# AD_Sensor_Module.net
KiCad netlist of a schematic drawn in Altium Designer
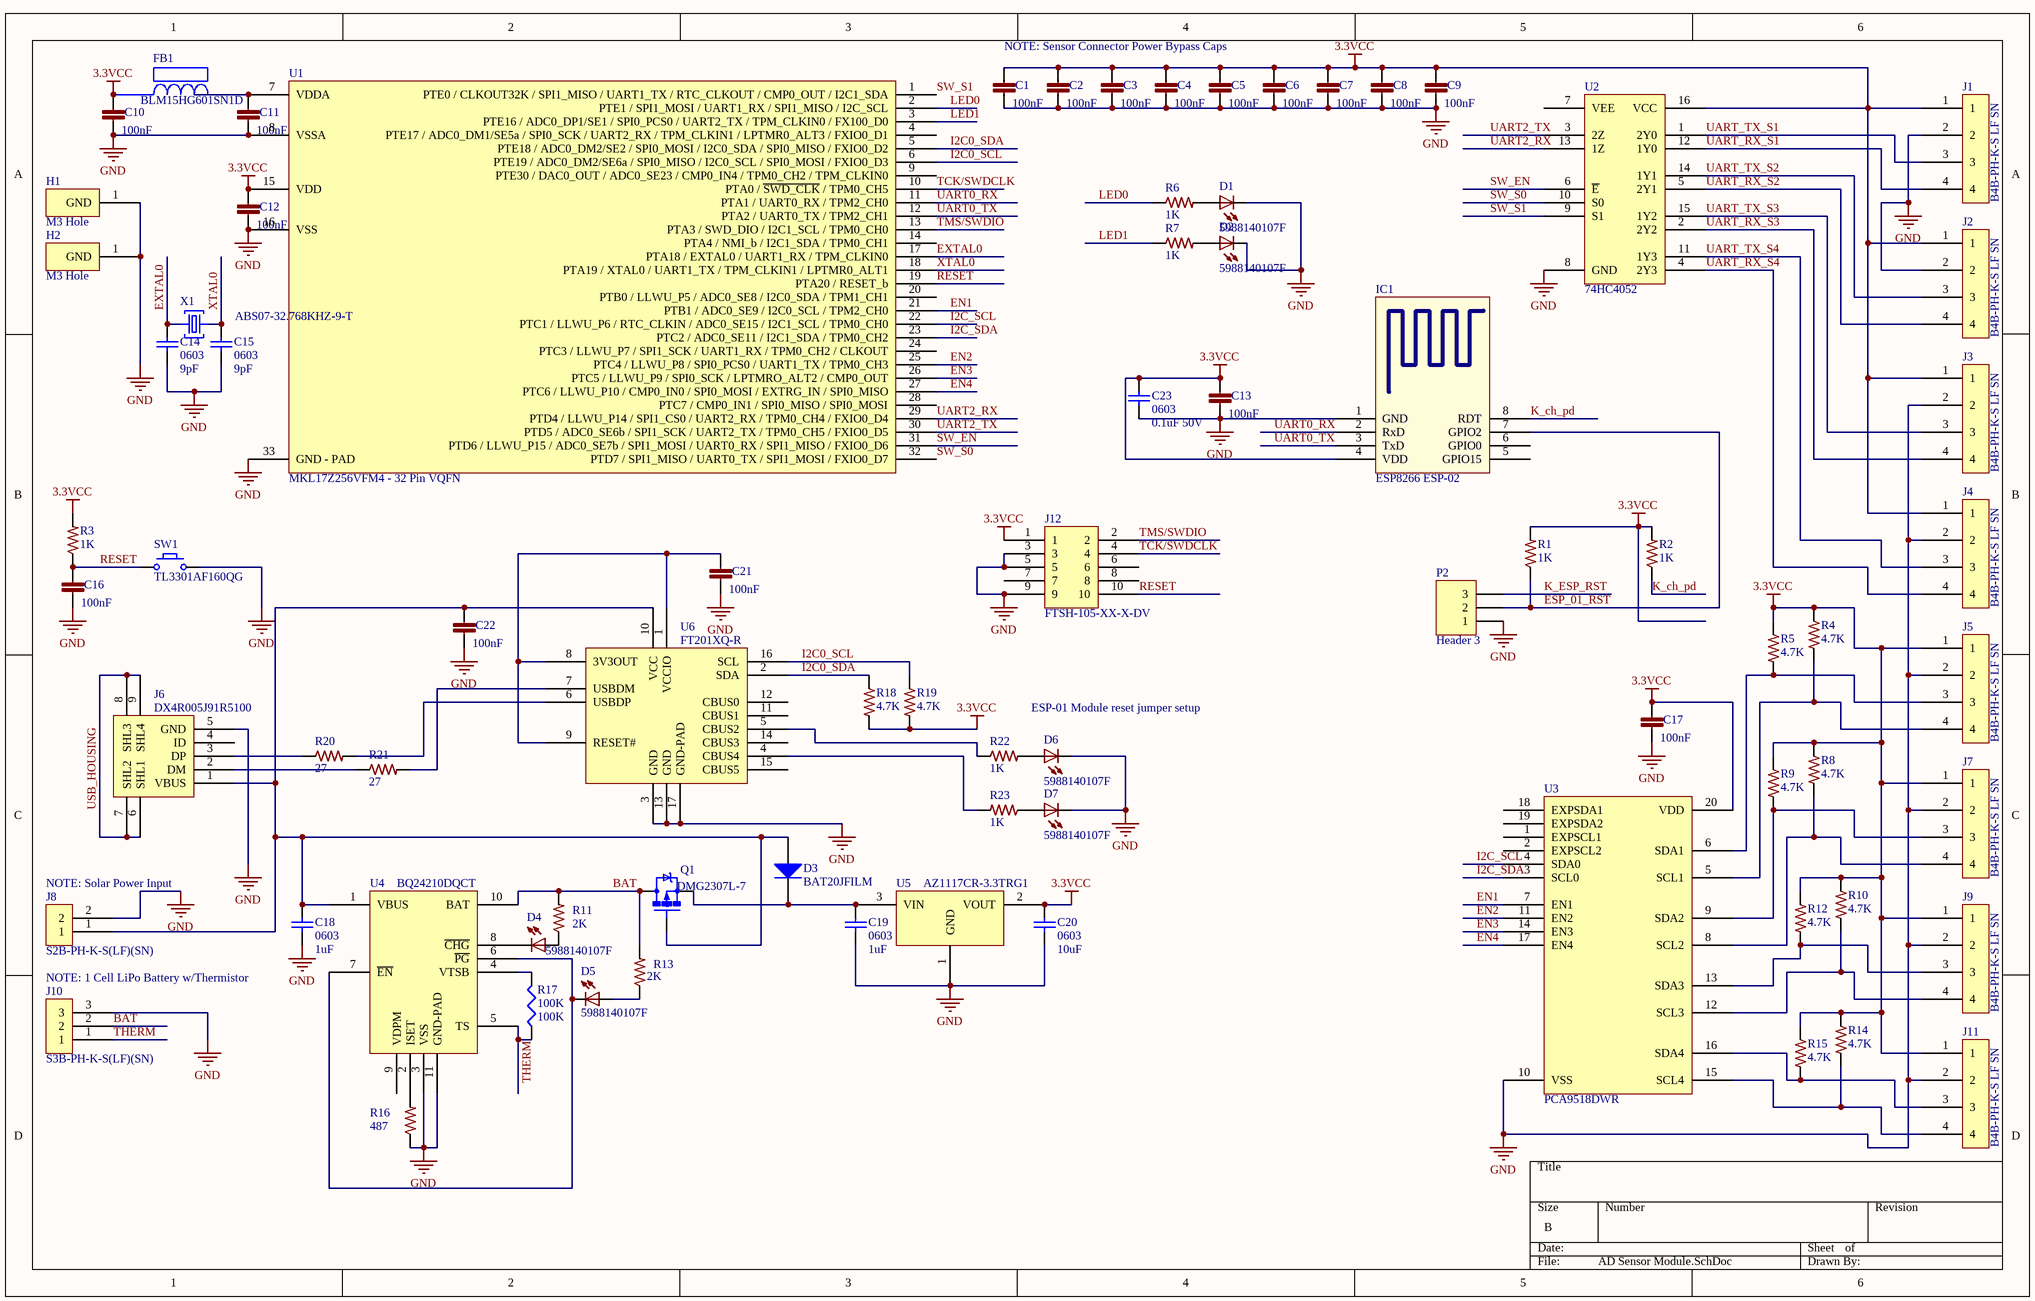
[diagram p0: AD Sensor Module.SchDoc]

(export (version "E")
  (design (tool "Eeschema 10.0.6"))
  (components
    (comp (ref "C1")
      (value "100nF")
      (footprint "C0402")
      (description "CAP CER 0402 100nF 16V 10% X7R")
      (fields
        (field (name "MANUFACTURERPARTNUMBER") "GRM155R71C104KA88D")
        (field (name "PUBLISHER") "UltiMachine")
      )
      (libsource (lib "3Delight") (part "GRM155R71C104KA88D"))
    )
    (comp (ref "C2")
      (value "100nF")
      (footprint "C0402")
      (description "CAP CER 0402 100nF 16V 10% X7R")
      (fields
        (field (name "MANUFACTURERPARTNUMBER") "GRM155R71C104KA88D")
        (field (name "PUBLISHER") "UltiMachine")
      )
      (libsource (lib "3Delight") (part "GRM155R71C104KA88D"))
    )
    (comp (ref "C3")
      (value "100nF")
      (footprint "C0402")
      (description "CAP CER 0402 100nF 16V 10% X7R")
      (fields
        (field (name "MANUFACTURERPARTNUMBER") "GRM155R71C104KA88D")
        (field (name "PUBLISHER") "UltiMachine")
      )
      (libsource (lib "3Delight") (part "GRM155R71C104KA88D"))
    )
    (comp (ref "C4")
      (value "100nF")
      (footprint "C0402")
      (description "CAP CER 0402 100nF 16V 10% X7R")
      (fields
        (field (name "MANUFACTURERPARTNUMBER") "GRM155R71C104KA88D")
        (field (name "PUBLISHER") "UltiMachine")
      )
      (libsource (lib "3Delight") (part "GRM155R71C104KA88D"))
    )
    (comp (ref "C5")
      (value "100nF")
      (footprint "C0402")
      (description "CAP CER 0402 100nF 16V 10% X7R")
      (fields
        (field (name "MANUFACTURERPARTNUMBER") "GRM155R71C104KA88D")
        (field (name "PUBLISHER") "UltiMachine")
      )
      (libsource (lib "3Delight") (part "GRM155R71C104KA88D"))
    )
    (comp (ref "C6")
      (value "100nF")
      (footprint "C0402")
      (description "CAP CER 0402 100nF 16V 10% X7R")
      (fields
        (field (name "MANUFACTURERPARTNUMBER") "GRM155R71C104KA88D")
        (field (name "PUBLISHER") "UltiMachine")
      )
      (libsource (lib "3Delight") (part "GRM155R71C104KA88D"))
    )
    (comp (ref "C7")
      (value "100nF")
      (footprint "C0402")
      (description "CAP CER 0402 100nF 16V 10% X7R")
      (fields
        (field (name "MANUFACTURERPARTNUMBER") "GRM155R71C104KA88D")
        (field (name "PUBLISHER") "UltiMachine")
      )
      (libsource (lib "3Delight") (part "GRM155R71C104KA88D"))
    )
    (comp (ref "C8")
      (value "100nF")
      (footprint "C0402")
      (description "CAP CER 0402 100nF 16V 10% X7R")
      (fields
        (field (name "MANUFACTURERPARTNUMBER") "GRM155R71C104KA88D")
        (field (name "PUBLISHER") "UltiMachine")
      )
      (libsource (lib "3Delight") (part "GRM155R71C104KA88D"))
    )
    (comp (ref "C9")
      (value "100nF")
      (footprint "C0402")
      (description "CAP CER 0402 100nF 16V 10% X7R")
      (fields
        (field (name "MANUFACTURERPARTNUMBER") "GRM155R71C104KA88D")
        (field (name "PUBLISHER") "UltiMachine")
      )
      (libsource (lib "3Delight") (part "GRM155R71C104KA88D"))
    )
    (comp (ref "C10")
      (value "100nF")
      (footprint "C0402")
      (description "CAP CER 0402 100nF 16V 10% X7R")
      (fields
        (field (name "MANUFACTURERPARTNUMBER") "GRM155R71C104KA88D")
        (field (name "PUBLISHER") "UltiMachine")
      )
      (libsource (lib "3Delight") (part "GRM155R71C104KA88D"))
    )
    (comp (ref "C11")
      (value "100nF")
      (footprint "C0402")
      (description "CAP CER 0402 100nF 16V 10% X7R")
      (fields
        (field (name "MANUFACTURERPARTNUMBER") "GRM155R71C104KA88D")
        (field (name "PUBLISHER") "UltiMachine")
      )
      (libsource (lib "3Delight") (part "GRM155R71C104KA88D"))
    )
    (comp (ref "C12")
      (value "100nF")
      (footprint "C0402")
      (description "CAP CER 0402 100nF 16V 10% X7R")
      (fields
        (field (name "MANUFACTURERPARTNUMBER") "GRM155R71C104KA88D")
        (field (name "PUBLISHER") "UltiMachine")
      )
      (libsource (lib "3Delight") (part "GRM155R71C104KA88D"))
    )
    (comp (ref "C13")
      (value "100nF")
      (footprint "C0402")
      (description "CAP CER 0402 100nF 16V 10% X7R")
      (fields
        (field (name "MANUFACTURERPARTNUMBER") "GRM155R71C104KA88D")
        (field (name "PUBLISHER") "UltiMachine")
      )
      (libsource (lib "3Delight") (part "GRM155R71C104KA88D"))
    )
    (comp (ref "C14")
      (value "0603")
      (footprint "C0603")
      (description "CAP CER 9PF 50V NP0 0603")
      (fields
        (field (name "MFR") "Samsung Electro-Mechanics America, Inc.")
        (field (name "TOLERANCE") "10%")
        (field (name "ALTIUM_VALUE") "9pF")
        (field (name "DESIGNER") "Adam Vadala-Roth")
      )
      (libsource (lib "Sensor Package") (part "CL10C090CB8NNNC"))
    )
    (comp (ref "C15")
      (value "0603")
      (footprint "C0603")
      (description "CAP CER 9PF 50V NP0 0603")
      (fields
        (field (name "MFR") "Samsung Electro-Mechanics America, Inc.")
        (field (name "TOLERANCE") "10%")
        (field (name "ALTIUM_VALUE") "9pF")
        (field (name "DESIGNER") "Adam Vadala-Roth")
      )
      (libsource (lib "Sensor Package") (part "CL10C090CB8NNNC"))
    )
    (comp (ref "C16")
      (value "100nF")
      (footprint "C0402")
      (description "CAP CER 0402 100nF 16V 10% X7R")
      (fields
        (field (name "MANUFACTURERPARTNUMBER") "GRM155R71C104KA88D")
        (field (name "PUBLISHER") "UltiMachine")
      )
      (libsource (lib "3Delight") (part "GRM155R71C104KA88D"))
    )
    (comp (ref "C17")
      (value "100nF")
      (footprint "C0402")
      (description "CAP CER 0402 100nF 16V 10% X7R")
      (fields
        (field (name "MANUFACTURERPARTNUMBER") "GRM155R71C104KA88D")
        (field (name "PUBLISHER") "UltiMachine")
      )
      (libsource (lib "3Delight") (part "GRM155R71C104KA88D"))
    )
    (comp (ref "C18")
      (value "0603")
      (footprint "C0603")
      (description "CAP CER 1UF 25V X5R 0402")
      (fields
        (field (name "MFR PART #") "CL05A105KA5NQNC")
        (field (name "MFR") "Samsung")
        (field (name "ALTIUM_VALUE") "1uF")
      )
      (libsource (lib "Sensor Package") (part "CL05A105KA5NQNC"))
    )
    (comp (ref "C19")
      (value "0603")
      (footprint "C0603")
      (description "CAP CER 1UF 25V X5R 0402")
      (fields
        (field (name "MFR PART #") "CL05A105KA5NQNC")
        (field (name "MFR") "Samsung")
        (field (name "ALTIUM_VALUE") "1uF")
      )
      (libsource (lib "Sensor Package") (part "CL05A105KA5NQNC"))
    )
    (comp (ref "C20")
      (value "0603")
      (footprint "C0603")
      (description "CAP CER 10UF 6.3V X5R 0603")
      (fields
        (field (name "MFR") "Samsung Electro-Mechanics America, Inc.")
        (field (name "TOLERANCE") "10%")
        (field (name "ALTIUM_VALUE") "10uF")
        (field (name "DESIGNER") "Adam Vadala-Roth")
      )
      (libsource (lib "Sensor Package") (part "CL10A106KQ8NNNC"))
    )
    (comp (ref "C21")
      (value "100nF")
      (footprint "C0402")
      (description "CAP CER 0402 100nF 16V 10% X7R")
      (fields
        (field (name "MANUFACTURERPARTNUMBER") "GRM155R71C104KA88D")
        (field (name "PUBLISHER") "UltiMachine")
      )
      (libsource (lib "3Delight") (part "GRM155R71C104KA88D"))
    )
    (comp (ref "C22")
      (value "100nF")
      (footprint "C0402")
      (description "CAP CER 0402 100nF 16V 10% X7R")
      (fields
        (field (name "MANUFACTURERPARTNUMBER") "GRM155R71C104KA88D")
        (field (name "PUBLISHER") "UltiMachine")
      )
      (libsource (lib "3Delight") (part "GRM155R71C104KA88D"))
    )
    (comp (ref "C23")
      (value "0603")
      (footprint "C0603")
      (description "CAP CER 0.1UF 50V 10% X7R 0603")
      (fields
        (field (name "MFR PART #") "CL10B104KB8SFNC")
        (field (name "MFR") "Samsung")
        (field (name "ALTIUM_VALUE") "0.1uF 50V")
      )
      (libsource (lib "Sensor Package") (part "CL10B104KB8SFNC"))
    )
    (comp (ref "D1")
      (value "5988140107F")
      (footprint "LED2012120")
      (description "LED 0805 Yellow")
      (fields (field (name "PUBLISHER") "UltiMachine"))
      (libsource (lib "Tigershark3D") (part "5988140107F"))
    )
    (comp (ref "D2")
      (value "5988140107F")
      (footprint "LED2012120")
      (description "LED 0805 Yellow")
      (fields (field (name "PUBLISHER") "UltiMachine"))
      (libsource (lib "Tigershark3D") (part "5988140107F"))
    )
    (comp (ref "D3")
      (value "BAT20JFILM")
      (footprint "BAT20JFILM - DIOM1712X11N")
      (description "DIODE SCHOTTKY 23V 1A SOD323")
      (fields
        (field (name "MFR") "ST Microelectronics")
        (field (name "PUBLISHER") "Altium Limited")
        (field (name "DESIGNER") "Adam J Valala-Roth")
      )
      (libsource (lib "Sensor Package") (part "BAT20JFILM"))
    )
    (comp (ref "D4")
      (value "5988140107F")
      (footprint "LED2012120")
      (description "LED 0805 Yellow")
      (fields (field (name "PUBLISHER") "UltiMachine"))
      (libsource (lib "Tigershark3D") (part "5988140107F"))
    )
    (comp (ref "D5")
      (value "5988140107F")
      (footprint "LED2012120")
      (description "LED 0805 Yellow")
      (fields (field (name "PUBLISHER") "UltiMachine"))
      (libsource (lib "Tigershark3D") (part "5988140107F"))
    )
    (comp (ref "D6")
      (value "5988140107F")
      (footprint "LED2012120")
      (description "LED 0805 Yellow")
      (fields (field (name "PUBLISHER") "UltiMachine"))
      (libsource (lib "Tigershark3D") (part "5988140107F"))
    )
    (comp (ref "D7")
      (value "5988140107F")
      (footprint "LED2012120")
      (description "LED 0805 Yellow")
      (fields (field (name "PUBLISHER") "UltiMachine"))
      (libsource (lib "Tigershark3D") (part "5988140107F"))
    )
    (comp (ref "FB1")
      (value "BLM15HG601SN1D")
      (footprint "BLM18PG121SN1D")
      (libsource (lib "Sensor Package") (part "BLM15HG601SN1D"))
    )
    (comp (ref "H1")
      (value "M3 Hole")
      (footprint "Hole-3mm")
      (description "3mm Hole")
      (libsource (lib "Sensor Package") (part "Hole"))
    )
    (comp (ref "H2")
      (value "M3 Hole")
      (footprint "Hole-3mm")
      (description "3mm Hole")
      (libsource (lib "Sensor Package") (part "Hole"))
    )
    (comp (ref "IC1")
      (value "ESP8266 ESP-02")
      (footprint "ESP8266 ESP-02")
      (libsource (lib "ESP8266") (part "ESP8266 ESP-02"))
    )
    (comp (ref "J1")
      (value "B4B-PH-K-S LF SN")
      (footprint "B4B-PH-K-S(LF)(SN)")
      (description "CONN HEADER PH TOP 4POS 2MM")
      (fields (field (name "MFR") "JST") (field (name "DESIGNER") "Adam Vadala-Roth"))
      (libsource (lib "Sensor Package") (part "B4B-PH-K-S LF SN"))
    )
    (comp (ref "J2")
      (value "B4B-PH-K-S LF SN")
      (footprint "B4B-PH-K-S(LF)(SN)")
      (description "CONN HEADER PH TOP 4POS 2MM")
      (fields (field (name "MFR") "JST") (field (name "DESIGNER") "Adam Vadala-Roth"))
      (libsource (lib "Sensor Package") (part "B4B-PH-K-S LF SN"))
    )
    (comp (ref "J3")
      (value "B4B-PH-K-S LF SN")
      (footprint "B4B-PH-K-S(LF)(SN)")
      (description "CONN HEADER PH TOP 4POS 2MM")
      (fields (field (name "MFR") "JST") (field (name "DESIGNER") "Adam Vadala-Roth"))
      (libsource (lib "Sensor Package") (part "B4B-PH-K-S LF SN"))
    )
    (comp (ref "J4")
      (value "B4B-PH-K-S LF SN")
      (footprint "B4B-PH-K-S(LF)(SN)")
      (description "CONN HEADER PH TOP 4POS 2MM")
      (fields (field (name "MFR") "JST") (field (name "DESIGNER") "Adam Vadala-Roth"))
      (libsource (lib "Sensor Package") (part "B4B-PH-K-S LF SN"))
    )
    (comp (ref "J5")
      (value "B4B-PH-K-S LF SN")
      (footprint "B4B-PH-K-S(LF)(SN)")
      (description "CONN HEADER PH TOP 4POS 2MM")
      (fields (field (name "MFR") "JST") (field (name "DESIGNER") "Adam Vadala-Roth"))
      (libsource (lib "Sensor Package") (part "B4B-PH-K-S LF SN"))
    )
    (comp (ref "J6")
      (value "DX4R005J91R5100")
      (footprint "Micro USB Circular Holes Only")
      (description "Micro USB Jack B")
      (libsource (lib "Sensor Package") (part "Micro USB"))
    )
    (comp (ref "J7")
      (value "B4B-PH-K-S LF SN")
      (footprint "B4B-PH-K-S(LF)(SN)")
      (description "CONN HEADER PH TOP 4POS 2MM")
      (fields (field (name "MFR") "JST") (field (name "DESIGNER") "Adam Vadala-Roth"))
      (libsource (lib "Sensor Package") (part "B4B-PH-K-S LF SN"))
    )
    (comp (ref "J8")
      (value "S2B-PH-K-S(LF)(SN)")
      (footprint "S2B-PH-K-S(LF)(SN)")
      (description "CONN HEADER PH SIDE 2POS 2MM")
      (fields (field (name "MFR") "JST") (field (name "DESIGNER") "Adam Vadala-Roth"))
      (libsource (lib "Sensor Package") (part "S2B-PH-K-S(LF)(SN)"))
    )
    (comp (ref "J9")
      (value "B4B-PH-K-S LF SN")
      (footprint "B4B-PH-K-S(LF)(SN)")
      (description "CONN HEADER PH TOP 4POS 2MM")
      (fields (field (name "MFR") "JST") (field (name "DESIGNER") "Adam Vadala-Roth"))
      (libsource (lib "Sensor Package") (part "B4B-PH-K-S LF SN"))
    )
    (comp (ref "J10")
      (value "S3B-PH-K-S(LF)(SN)")
      (footprint "S3B-PH-K-S(LF)(SN)")
      (description "CONN HEADER PH SIDE 2POS 2MM")
      (fields (field (name "MFR") "JST") (field (name "DESIGNER") "Adam Vadala-Roth"))
      (libsource (lib "Sensor Package") (part "S3B-PH-K-S(LF)(SN)"))
    )
    (comp (ref "J11")
      (value "B4B-PH-K-S LF SN")
      (footprint "B4B-PH-K-S(LF)(SN)")
      (description "CONN HEADER PH TOP 4POS 2MM")
      (fields (field (name "MFR") "JST") (field (name "DESIGNER") "Adam Vadala-Roth"))
      (libsource (lib "Sensor Package") (part "B4B-PH-K-S LF SN"))
    )
    (comp (ref "J12")
      (value "FTSH-105-XX-X-DV")
      (footprint "FTSH-105-XX-X-DV")
      (description "FTSH-105-XX-X-DV ARM COrtex JTAG")
      (fields (field (name "DESIGNER") "*"))
      (libsource (lib "Sensor Package") (part "FTSH-105-XX-X-DV"))
    )
    (comp (ref "P2")
      (value "Header 3")
      (footprint "HDR1X3")
      (description "Header, 3-Pin")
      (fields (field (name "PUBLISHER") "Altium Limited"))
      (libsource (lib "Miscellaneous Connectors") (part "Header 3"))
    )
    (comp (ref "Q1")
      (value "DMG2307L-7")
      (footprint "DMG2307L-7 - SOT92P240X102-3N")
      (description "MOSFET P-CH 30V 2.5A SOT-23")
      (fields (field (name "MFR") "Diodes Incorporated") (field (name "PUBLISHER") "Adam Vadala-Roth"))
      (libsource (lib "Sensor Package") (part "DMG2307L-7"))
    )
    (comp (ref "R1")
      (value "1K")
      (footprint "R0603")
      (description "RES 0603 1K 100mW 1%")
      (fields
        (field (name "MANUFACTURERPARTNUMBER") "ERJ-3EKF1001V")
        (field (name "PUBLISHER") "UltiMachine")
      )
      (libsource (lib "3Delight") (part "ERJ-3EKF1001V"))
    )
    (comp (ref "R2")
      (value "1K")
      (footprint "R0603")
      (description "RES 0603 1K 100mW 1%")
      (fields
        (field (name "MANUFACTURERPARTNUMBER") "ERJ-3EKF1001V")
        (field (name "PUBLISHER") "UltiMachine")
      )
      (libsource (lib "3Delight") (part "ERJ-3EKF1001V"))
    )
    (comp (ref "R3")
      (value "1K")
      (footprint "R0603")
      (description "RES 0603 1K 100mW 1%")
      (fields
        (field (name "MANUFACTURERPARTNUMBER") "ERJ-3EKF1001V")
        (field (name "PUBLISHER") "UltiMachine")
      )
      (libsource (lib "3Delight") (part "ERJ-3EKF1001V"))
    )
    (comp (ref "R4")
      (value "4.7K")
      (footprint "R0603")
      (description "RES 0603 4.7K 100mW 1%")
      (fields (field (name "MANUFACTURERPARTNUMBER") "ERJ3EKF4701V") (field (name "PUBLISHER") "UltiMachine"))
      (libsource (lib "Tigershark3D") (part "ERJ3EKF4701V"))
    )
    (comp (ref "R5")
      (value "4.7K")
      (footprint "R0603")
      (description "RES 0603 4.7K 100mW 1%")
      (fields (field (name "MANUFACTURERPARTNUMBER") "ERJ3EKF4701V") (field (name "PUBLISHER") "UltiMachine"))
      (libsource (lib "Tigershark3D") (part "ERJ3EKF4701V"))
    )
    (comp (ref "R6")
      (value "1K")
      (footprint "R0603")
      (description "RES 0603 1K 100mW 1%")
      (fields
        (field (name "MANUFACTURERPARTNUMBER") "ERJ-3EKF1001V")
        (field (name "PUBLISHER") "UltiMachine")
      )
      (libsource (lib "Tigershark3D") (part "ERJ-3EKF1001V"))
    )
    (comp (ref "R7")
      (value "1K")
      (footprint "R0603")
      (description "RES 0603 1K 100mW 1%")
      (fields
        (field (name "MANUFACTURERPARTNUMBER") "ERJ-3EKF1001V")
        (field (name "PUBLISHER") "UltiMachine")
      )
      (libsource (lib "Tigershark3D") (part "ERJ-3EKF1001V"))
    )
    (comp (ref "R8")
      (value "4.7K")
      (footprint "R0603")
      (description "RES 0603 4.7K 100mW 1%")
      (fields (field (name "MANUFACTURERPARTNUMBER") "ERJ3EKF4701V") (field (name "PUBLISHER") "UltiMachine"))
      (libsource (lib "Tigershark3D") (part "ERJ3EKF4701V"))
    )
    (comp (ref "R9")
      (value "4.7K")
      (footprint "R0603")
      (description "RES 0603 4.7K 100mW 1%")
      (fields (field (name "MANUFACTURERPARTNUMBER") "ERJ3EKF4701V") (field (name "PUBLISHER") "UltiMachine"))
      (libsource (lib "Tigershark3D") (part "ERJ3EKF4701V"))
    )
    (comp (ref "R10")
      (value "4.7K")
      (footprint "R0603")
      (description "RES 0603 4.7K 100mW 1%")
      (fields (field (name "MANUFACTURERPARTNUMBER") "ERJ3EKF4701V") (field (name "PUBLISHER") "UltiMachine"))
      (libsource (lib "Tigershark3D") (part "ERJ3EKF4701V"))
    )
    (comp (ref "R11")
      (value "2K")
      (footprint "R0805")
      (description "RES SMD 2K OHM 1% 1/8W 0805")
      (fields
        (field (name "MFR") "Panasonic Electronic Components")
        (field (name "TOLERANCE") "1%")
        (field (name "DESIGNER") "Adam Vadala-Roth")
      )
      (libsource (lib "Sensor Package") (part "ERJ-6ENF2001V"))
    )
    (comp (ref "R12")
      (value "4.7K")
      (footprint "R0603")
      (description "RES 0603 4.7K 100mW 1%")
      (fields (field (name "MANUFACTURERPARTNUMBER") "ERJ3EKF4701V") (field (name "PUBLISHER") "UltiMachine"))
      (libsource (lib "Tigershark3D") (part "ERJ3EKF4701V"))
    )
    (comp (ref "R13")
      (value "2K")
      (footprint "R0805")
      (description "RES SMD 2K OHM 1% 1/8W 0805")
      (fields
        (field (name "MFR") "Panasonic Electronic Components")
        (field (name "TOLERANCE") "1%")
        (field (name "DESIGNER") "Adam Vadala-Roth")
      )
      (libsource (lib "Sensor Package") (part "ERJ-6ENF2001V"))
    )
    (comp (ref "R14")
      (value "4.7K")
      (footprint "R0603")
      (description "RES 0603 4.7K 100mW 1%")
      (fields (field (name "MANUFACTURERPARTNUMBER") "ERJ3EKF4701V") (field (name "PUBLISHER") "UltiMachine"))
      (libsource (lib "Tigershark3D") (part "ERJ3EKF4701V"))
    )
    (comp (ref "R15")
      (value "4.7K")
      (footprint "R0603")
      (description "RES 0603 4.7K 100mW 1%")
      (fields (field (name "MANUFACTURERPARTNUMBER") "ERJ3EKF4701V") (field (name "PUBLISHER") "UltiMachine"))
      (libsource (lib "Tigershark3D") (part "ERJ3EKF4701V"))
    )
    (comp (ref "R16")
      (value "487")
      (footprint "R0402")
      (description "RES SMD 487 OHM 1% 1/16W 0402")
      (fields
        (field (name "MFR") "Samsung Electro-Mechanics America, Inc.")
        (field (name "TOLERANCE") "1%")
        (field (name "DESIGNER") "Adam Vadala-Roth")
      )
      (libsource (lib "Sensor Package") (part "RC1005F4870CS"))
    )
    (comp (ref "R17")
      (value "100K")
      (footprint "R0402")
      (description "Standin 0402")
      (fields (field (name "ALTIUM_VALUE") "100K"))
      (libsource (lib "Sensor Package") (part "Standin 0402"))
    )
    (comp (ref "R18")
      (value "4.7K")
      (footprint "R0603")
      (description "RES 0603 4.7K 100mW 1%")
      (fields (field (name "MANUFACTURERPARTNUMBER") "ERJ3EKF4701V") (field (name "PUBLISHER") "UltiMachine"))
      (libsource (lib "Tigershark3D") (part "ERJ3EKF4701V"))
    )
    (comp (ref "R19")
      (value "4.7K")
      (footprint "R0603")
      (description "RES 0603 4.7K 100mW 1%")
      (fields (field (name "MANUFACTURERPARTNUMBER") "ERJ3EKF4701V") (field (name "PUBLISHER") "UltiMachine"))
      (libsource (lib "Tigershark3D") (part "ERJ3EKF4701V"))
    )
    (comp (ref "R20")
      (value "27")
      (footprint "R0402")
      (description "RES SMD 27 OHM 0.5% 1/16W 0402")
      (fields
        (field (name "MFR") "Susumu")
        (field (name "TOLERANCE") "0.5%")
        (field (name "DESIGNER") "Adam Vadala-Roth")
      )
      (libsource (lib "Sensor Package") (part "RR0510R-270-D"))
    )
    (comp (ref "R21")
      (value "27")
      (footprint "R0402")
      (description "RES SMD 27 OHM 0.5% 1/16W 0402")
      (fields
        (field (name "MFR") "Susumu")
        (field (name "TOLERANCE") "0.5%")
        (field (name "DESIGNER") "Adam Vadala-Roth")
      )
      (libsource (lib "Sensor Package") (part "RR0510R-270-D"))
    )
    (comp (ref "R22")
      (value "1K")
      (footprint "R0603")
      (description "RES 0603 1K 100mW 1%")
      (fields
        (field (name "MANUFACTURERPARTNUMBER") "ERJ-3EKF1001V")
        (field (name "PUBLISHER") "UltiMachine")
      )
      (libsource (lib "Tigershark3D") (part "ERJ-3EKF1001V"))
    )
    (comp (ref "R23")
      (value "1K")
      (footprint "R0603")
      (description "RES 0603 1K 100mW 1%")
      (fields
        (field (name "MANUFACTURERPARTNUMBER") "ERJ-3EKF1001V")
        (field (name "PUBLISHER") "UltiMachine")
      )
      (libsource (lib "Tigershark3D") (part "ERJ-3EKF1001V"))
    )
    (comp (ref "SW1")
      (value "TL3301AF160QG")
      (footprint "TL3301AF160QG")
      (libsource (lib "MongoosMini") (part "TL3301AF160QG"))
    )
    (comp (ref "U1")
      (value "MKL17Z256VFM4 - 32 Pin VQFN")
      (footprint "MKL17Z256VFM4 - QFN50P500X500X65_HS-33N")
      (description "ARM Cortex M0+ Microcontroller for Low Power Applications, MKL1x Series")
      (fields
        (field (name "MFR") "NXP - FreeScale")
        (field (name "VOLTAGE") "1.7-3.3VDC")
        (field (name "DESIGNER") "Adam Vadala-Roth")
      )
      (libsource (lib "Sensor Package") (part "MKL17Z256VFM4 - 32 Pin VQFN"))
    )
    (comp (ref "U2")
      (value "74HC4052")
      (footprint "74HC4052")
      (description "Dual 4-channel analog multiplexer/demultiplexer")
      (fields (field (name "MFR") "NXP"))
      (libsource (lib "Sensor Package") (part "74HC4052"))
    )
    (comp (ref "U3")
      (value "PCA9518DWR")
      (footprint "PCA9518DWR")
      (description "IC EXPANDABLE 5CH I2C HUB 20SOIC")
      (fields (field (name "MFR") "Ti"))
      (libsource (lib "Sensor Package") (part "PCA9518DWR"))
    )
    (comp (ref "U4")
      (value "BQ24210DQCT")
      (footprint "bq24210 - QFN50P300X200X80-10N")
      (description "IC BATT CHARGER LI-ION 10WSON (VBUS and Solar Voltaic Cell)")
      (fields (field (name "MFR") "Texas Instruments") (field (name "DESIGNER") "Adam J Vadala-Roth"))
      (libsource (lib "Sensor Package") (part "BQ24210DQCT"))
    )
    (comp (ref "U5")
      (value "AZ1117CR-3.3TRG1")
      (footprint "AZ1117CR-3.3TRG1 - SOT89-150P410X160-3N")
      (description "IC REG LDO 3.3V 0.8A SOT89")
      (fields
        (field (name "MFR") "Diodes Inc")
        (field (name "VOLTAGE") "3V3")
        (field (name "DESIGNER") "Adam Vadala-Roth")
      )
      (libsource (lib "Sensor Package") (part "AZ1117CR-3.3TRG1"))
    )
    (comp (ref "U6")
      (value "FT201XQ-R")
      (footprint "FT201XQ-R - QFN65P400X400X80_HS-17N")
      (description "IC USB FS I2C 16QFN")
      (fields
        (field (name "MFR") "FTDI")
        (field (name "VOLTAGE") "3V3/5V")
        (field (name "DESIGNER") "Adam Vadala-Roth")
      )
      (libsource (lib "Sensor Package") (part "FT201XQ-R"))
    )
    (comp (ref "X1")
      (value "ABS07-32.768KHZ-9-T")
      (footprint "ABS07-32.768KHZ-9-T")
      (description "32.768kHz ±20ppm Crystal 9pF 70 kOhm -40°C ~ 85°C Surface Mount 2-SMD")
      (fields
        (field (name "MFR") "Abracon LLC")
        (field (name "TOLERANCE") "±20ppm")
        (field (name "DESIGNER") "Adam Vadala-Roth")
      )
      (libsource (lib "Sensor Package") (part "ABS07-32.768KHZ-9-T"))
    )
  )
  (nets
    (net (code "1") (name "/BAT") (class "Default")
      (node (ref "J10") (pin "2") (pinfunction "2_2") (pintype "passive"))
      (node (ref "Q1") (pin "3") (pinfunction "D_3") (pintype "passive"))
      (node (ref "R11") (pin "2") (pinfunction "2_2") (pintype "passive"))
      (node (ref "R13") (pin "2") (pinfunction "2_2") (pintype "passive"))
      (node (ref "U4") (pin "10") (pinfunction "BAT_10") (pintype "passive"))
    )
    (net (code "2") (name "/EN1") (class "Default")
      (node (ref "U1") (pin "21") (pinfunction "PTB1_/_ADC0_SE9_/_I2C0_SCL_/_TPM2_CH0_21") (pintype "passive"))
      (node (ref "U3") (pin "7") (pinfunction "EN1_7") (pintype "passive"))
    )
    (net (code "3") (name "/EN2") (class "Default")
      (node (ref "U1") (pin "25") (pinfunction "PTC4_/_LLWU_P8_/_SPI0_PCS0_/_UART1_TX_/_TPM0_CH3_25") (pintype "passive"))
      (node (ref "U3") (pin "11") (pinfunction "EN2_11") (pintype "passive"))
    )
    (net (code "4") (name "/EN3") (class "Default")
      (node (ref "U1") (pin "26") (pinfunction "PTC5_/_LLWU_P9_/_SPI0_SCK_/_LPTMRO_ALT2_/_CMP0_OUT_26") (pintype "passive"))
      (node (ref "U3") (pin "14") (pinfunction "EN3_14") (pintype "passive"))
    )
    (net (code "5") (name "/EN4") (class "Default")
      (node (ref "U1") (pin "27") (pinfunction "PTC6_/_LLWU_P10_/_CMP0_IN0_/_SPI0_MOSI_/_EXTRG_IN_/_SPI0_MISO_27") (pintype "passive"))
      (node (ref "U3") (pin "17") (pinfunction "EN4_17") (pintype "passive"))
    )
    (net (code "6") (name "/ESP_01_RST") (class "Default")
      (node (ref "IC1") (pin "7") (pinfunction "GPIO2_7") (pintype "passive"))
      (node (ref "P2") (pin "2") (pinfunction "2_2") (pintype "passive"))
      (node (ref "R1") (pin "1") (pinfunction "1_1") (pintype "passive"))
    )
    (net (code "7") (name "/EXTAL0") (class "Default")
      (node (ref "C14") (pin "2") (pinfunction "2_2") (pintype "passive"))
      (node (ref "U1") (pin "17") (pinfunction "PTA18_/_EXTAL0_/_UART1_RX_/_TPM_CLKIN0_17") (pintype "passive"))
      (node (ref "X1") (pin "1") (pinfunction "C1_1") (pintype "passive"))
    )
    (net (code "8") (name "/I2C0_SCL") (class "Default")
      (node (ref "R19") (pin "1") (pinfunction "1_1") (pintype "passive"))
      (node (ref "U1") (pin "6") (pinfunction "PTE19_/_ADC0_DM2/SE6a_/_SPI0_MISO_/_I2C0_SCL_/_SPI0_MOSI_/_FXIO0_D3_6") (pintype "passive"))
      (node (ref "U6") (pin "16") (pinfunction "SCL_16") (pintype "passive"))
    )
    (net (code "9") (name "/I2C0_SDA") (class "Default")
      (node (ref "R18") (pin "1") (pinfunction "1_1") (pintype "passive"))
      (node (ref "U1") (pin "5") (pinfunction "PTE18_/_ADC0_DM2/SE2_/_SPI0_MOSI_/_I2C0_SDA_/_SPI0_MISO_/_FXIO0_D2_5") (pintype "passive"))
      (node (ref "U6") (pin "2") (pinfunction "SDA_2") (pintype "passive"))
    )
    (net (code "10") (name "/I2C_SCL") (class "Default")
      (node (ref "U1") (pin "22") (pinfunction "PTC1_/_LLWU_P6_/_RTC_CLKIN_/_ADC0_SE15_/_I2C1_SCL_/_TPM0_CH0_22") (pintype "passive"))
      (node (ref "U3") (pin "4") (pinfunction "SDA0_4") (pintype "passive"))
    )
    (net (code "11") (name "/I2C_SDA") (class "Default")
      (node (ref "U1") (pin "23") (pinfunction "PTC2_/_ADC0_SE11_/_I2C1_SDA_/_TPM0_CH2_23") (pintype "passive"))
      (node (ref "U3") (pin "3") (pinfunction "SCL0_3") (pintype "passive"))
    )
    (net (code "12") (name "/K_ESP_RST") (class "Default")
      (node (ref "P2") (pin "3") (pinfunction "3_3") (pintype "passive"))
    )
    (net (code "13") (name "/K_ch_pd") (class "Default")
      (node (ref "IC1") (pin "8") (pinfunction "RDT_8") (pintype "passive"))
      (node (ref "R2") (pin "1") (pinfunction "1_1") (pintype "passive"))
    )
    (net (code "14") (name "/LED0") (class "Default")
      (node (ref "R6") (pin "1") (pinfunction "1_1") (pintype "passive"))
      (node (ref "U1") (pin "2") (pinfunction "PTE1_/_SPI1_MOSI_/_UART1_RX_/_SPI1_MISO_/_I2C_SCL_2") (pintype "passive"))
    )
    (net (code "15") (name "/LED1") (class "Default")
      (node (ref "R7") (pin "1") (pinfunction "1_1") (pintype "passive"))
      (node (ref "U1") (pin "3") (pinfunction "PTE16_/_ADC0_DP1/SE1_/_SPI0_PCS0_/_UART2_TX_/_TPM_CLKIN0_/_FX100_D0_3") (pintype "passive"))
    )
    (net (code "16") (name "/RESET") (class "Default")
      (node (ref "C16") (pin "1") (pinfunction "1_1") (pintype "passive"))
      (node (ref "J12") (pin "10") (pinfunction "10_10") (pintype "passive"))
      (node (ref "R3") (pin "1") (pinfunction "1_1") (pintype "passive"))
      (node (ref "SW1") (pin "1") (pintype "passive"))
      (node (ref "U1") (pin "19") (pinfunction "PTA20_/_RESET_b_19") (pintype "passive"))
    )
    (net (code "17") (name "/SW_EN") (class "Default")
      (node (ref "U1") (pin "31") (pinfunction "PTD6_/_LLWU_P15_/_ADC0_SE7b_/_SPI1_MOSI_/_UART0_RX_/_SPI1_MISO_/_FXIO0_D6_31") (pintype "passive"))
      (node (ref "U2") (pin "6") (pinfunction "~{E}_6") (pintype "passive"))
    )
    (net (code "18") (name "/SW_S0") (class "Default")
      (node (ref "U1") (pin "32") (pinfunction "PTD7_/_SPI1_MISO_/_UART0_TX_/_SPI1_MOSI_/_FXIO0_D7_32") (pintype "passive"))
      (node (ref "U2") (pin "10") (pinfunction "S0_10") (pintype "passive"))
    )
    (net (code "19") (name "/SW_S1") (class "Default")
      (node (ref "U1") (pin "1") (pinfunction "PTE0_/_CLKOUT32K_/_SPI1_MISO_/_UART1_TX_/_RTC_CLKOUT_/_CMP0_OUT_/_I2C1_SDA_1") (pintype "passive"))
      (node (ref "U2") (pin "9") (pinfunction "S1_9") (pintype "passive"))
    )
    (net (code "20") (name "/TCK{slash}SWDCLK") (class "Default")
      (node (ref "J12") (pin "4") (pinfunction "4_4") (pintype "passive"))
      (node (ref "U1") (pin "10") (pinfunction "PTA0_/_~{SWD_CLK}_/_TPM0_CH5_10") (pintype "passive"))
    )
    (net (code "21") (name "/THERM") (class "Default")
      (node (ref "J10") (pin "1") (pinfunction "1_1") (pintype "passive"))
      (node (ref "R17") (pin "1") (pinfunction "1_1") (pintype "passive"))
      (node (ref "U4") (pin "5") (pinfunction "TS_5") (pintype "passive"))
    )
    (net (code "22") (name "/TMS{slash}SWDIO") (class "Default")
      (node (ref "J12") (pin "2") (pinfunction "2_2") (pintype "passive"))
      (node (ref "U1") (pin "13") (pinfunction "PTA3_/_SWD_DIO_/_I2C1_SCL_/_TPM0_CH0_13") (pintype "passive"))
    )
    (net (code "23") (name "/UART0_RX") (class "Default")
      (node (ref "IC1") (pin "2") (pinfunction "RxD_2") (pintype "passive"))
      (node (ref "U1") (pin "11") (pinfunction "PTA1_/_UART0_RX_/_TPM2_CH0_11") (pintype "passive"))
    )
    (net (code "24") (name "/UART0_TX") (class "Default")
      (node (ref "IC1") (pin "3") (pinfunction "TxD_3") (pintype "passive"))
      (node (ref "U1") (pin "12") (pinfunction "PTA2_/_UART0_TX_/_TPM2_CH1_12") (pintype "passive"))
    )
    (net (code "25") (name "/UART2_RX") (class "Default")
      (node (ref "U1") (pin "29") (pinfunction "PTD4_/_LLWU_P14_/_SPI1_CS0_/_UART2_RX_/_TPM0_CH4_/_FXIO0_D4_29") (pintype "passive"))
      (node (ref "U2") (pin "13") (pinfunction "1Z_13") (pintype "passive"))
    )
    (net (code "26") (name "/UART2_TX") (class "Default")
      (node (ref "U1") (pin "30") (pinfunction "PTD5_/_ADC0_SE6b_/_SPI1_SCK_/_UART2_TX_/_TPM0_CH5_/_FXIO0_D5_30") (pintype "passive"))
      (node (ref "U2") (pin "3") (pinfunction "2Z_3") (pintype "passive"))
    )
    (net (code "27") (name "/UART_RX_S1") (class "Default")
      (node (ref "J1") (pin "4") (pinfunction "4_4") (pintype "passive"))
      (node (ref "U2") (pin "12") (pinfunction "1Y0_12") (pintype "passive"))
    )
    (net (code "28") (name "/UART_RX_S2") (class "Default")
      (node (ref "J2") (pin "4") (pinfunction "4_4") (pintype "passive"))
      (node (ref "U2") (pin "5") (pinfunction "2Y1_5") (pintype "passive"))
    )
    (net (code "29") (name "/UART_RX_S3") (class "Default")
      (node (ref "J3") (pin "4") (pinfunction "4_4") (pintype "passive"))
      (node (ref "U2") (pin "2") (pinfunction "2Y2_2") (pintype "passive"))
    )
    (net (code "30") (name "/UART_RX_S4") (class "Default")
      (node (ref "J4") (pin "4") (pinfunction "4_4") (pintype "passive"))
      (node (ref "U2") (pin "4") (pinfunction "2Y3_4") (pintype "passive"))
    )
    (net (code "31") (name "/UART_TX_S1") (class "Default")
      (node (ref "J1") (pin "3") (pinfunction "3_3") (pintype "passive"))
      (node (ref "U2") (pin "1") (pinfunction "2Y0_1") (pintype "passive"))
    )
    (net (code "32") (name "/UART_TX_S2") (class "Default")
      (node (ref "J2") (pin "3") (pinfunction "3_3") (pintype "passive"))
      (node (ref "U2") (pin "14") (pinfunction "1Y1_14") (pintype "passive"))
    )
    (net (code "33") (name "/UART_TX_S3") (class "Default")
      (node (ref "J3") (pin "3") (pinfunction "3_3") (pintype "passive"))
      (node (ref "U2") (pin "15") (pinfunction "1Y2_15") (pintype "passive"))
    )
    (net (code "34") (name "/UART_TX_S4") (class "Default")
      (node (ref "J4") (pin "3") (pinfunction "3_3") (pintype "passive"))
      (node (ref "U2") (pin "11") (pinfunction "1Y3_11") (pintype "passive"))
    )
    (net (code "35") (name "/USB_HOUSING") (class "Default")
      (node (ref "J6") (pin "6") (pinfunction "SHL1_6") (pintype "passive"))
      (node (ref "J6") (pin "7") (pinfunction "SHL2_7") (pintype "passive"))
      (node (ref "J6") (pin "8") (pinfunction "SHL3_8") (pintype "passive"))
      (node (ref "J6") (pin "9") (pinfunction "SHL4_9") (pintype "passive"))
    )
    (net (code "36") (name "/XTAL0") (class "Default")
      (node (ref "C15") (pin "2") (pinfunction "2_2") (pintype "passive"))
      (node (ref "U1") (pin "18") (pinfunction "PTA19_/_XTAL0_/_UART1_TX_/_TPM_CLKIN1_/_LPTMR0_ALT1_18") (pintype "passive"))
      (node (ref "X1") (pin "2") (pinfunction "C2_2") (pintype "passive"))
    )
    (net (code "37") (name "3.3VCC") (class "Default")
      (node (ref "C1") (pin "1") (pinfunction "1_1") (pintype "passive"))
      (node (ref "C10") (pin "1") (pinfunction "1_1") (pintype "passive"))
      (node (ref "C12") (pin "1") (pinfunction "1_1") (pintype "passive"))
      (node (ref "C13") (pin "1") (pinfunction "1_1") (pintype "passive"))
      (node (ref "C17") (pin "1") (pinfunction "1_1") (pintype "passive"))
      (node (ref "C2") (pin "1") (pinfunction "1_1") (pintype "passive"))
      (node (ref "C20") (pin "2") (pinfunction "2_2") (pintype "passive"))
      (node (ref "C23") (pin "2") (pinfunction "2_2") (pintype "passive"))
      (node (ref "C3") (pin "1") (pinfunction "1_1") (pintype "passive"))
      (node (ref "C4") (pin "1") (pinfunction "1_1") (pintype "passive"))
      (node (ref "C5") (pin "1") (pinfunction "1_1") (pintype "passive"))
      (node (ref "C6") (pin "1") (pinfunction "1_1") (pintype "passive"))
      (node (ref "C7") (pin "1") (pinfunction "1_1") (pintype "passive"))
      (node (ref "C8") (pin "1") (pinfunction "1_1") (pintype "passive"))
      (node (ref "C9") (pin "1") (pinfunction "1_1") (pintype "passive"))
      (node (ref "FB1") (pin "1") (pinfunction "1_1") (pintype "passive"))
      (node (ref "IC1") (pin "4") (pinfunction "VDD_4") (pintype "passive"))
      (node (ref "J1") (pin "1") (pinfunction "1_1") (pintype "passive"))
      (node (ref "J11") (pin "1") (pinfunction "1_1") (pintype "passive"))
      (node (ref "J12") (pin "1") (pinfunction "1_1") (pintype "passive"))
      (node (ref "J2") (pin "1") (pinfunction "1_1") (pintype "passive"))
      (node (ref "J3") (pin "1") (pinfunction "1_1") (pintype "passive"))
      (node (ref "J4") (pin "1") (pinfunction "1_1") (pintype "passive"))
      (node (ref "J5") (pin "1") (pinfunction "1_1") (pintype "passive"))
      (node (ref "J7") (pin "1") (pinfunction "1_1") (pintype "passive"))
      (node (ref "J9") (pin "1") (pinfunction "1_1") (pintype "passive"))
      (node (ref "R1") (pin "2") (pinfunction "2_2") (pintype "passive"))
      (node (ref "R10") (pin "1") (pinfunction "1_1") (pintype "passive"))
      (node (ref "R12") (pin "1") (pinfunction "1_1") (pintype "passive"))
      (node (ref "R14") (pin "1") (pinfunction "1_1") (pintype "passive"))
      (node (ref "R15") (pin "1") (pinfunction "1_1") (pintype "passive"))
      (node (ref "R18") (pin "2") (pinfunction "2_2") (pintype "passive"))
      (node (ref "R19") (pin "2") (pinfunction "2_2") (pintype "passive"))
      (node (ref "R2") (pin "2") (pinfunction "2_2") (pintype "passive"))
      (node (ref "R3") (pin "2") (pinfunction "2_2") (pintype "passive"))
      (node (ref "R4") (pin "1") (pinfunction "1_1") (pintype "passive"))
      (node (ref "R5") (pin "1") (pinfunction "1_1") (pintype "passive"))
      (node (ref "R8") (pin "1") (pinfunction "1_1") (pintype "passive"))
      (node (ref "R9") (pin "1") (pinfunction "1_1") (pintype "passive"))
      (node (ref "U1") (pin "15") (pinfunction "VDD_15") (pintype "passive"))
      (node (ref "U2") (pin "16") (pinfunction "VCC_16") (pintype "passive"))
      (node (ref "U3") (pin "20") (pinfunction "VDD_20") (pintype "passive"))
      (node (ref "U5") (pin "2") (pinfunction "VOUT_2") (pintype "passive"))
    )
    (net (code "38") (name "GND") (class "Default")
      (node (ref "C1") (pin "2") (pinfunction "2_2") (pintype "passive"))
      (node (ref "C10") (pin "2") (pinfunction "2_2") (pintype "passive"))
      (node (ref "C11") (pin "2") (pinfunction "2_2") (pintype "passive"))
      (node (ref "C12") (pin "2") (pinfunction "2_2") (pintype "passive"))
      (node (ref "C13") (pin "2") (pinfunction "2_2") (pintype "passive"))
      (node (ref "C14") (pin "1") (pinfunction "1_1") (pintype "passive"))
      (node (ref "C15") (pin "1") (pinfunction "1_1") (pintype "passive"))
      (node (ref "C16") (pin "2") (pinfunction "2_2") (pintype "passive"))
      (node (ref "C17") (pin "2") (pinfunction "2_2") (pintype "passive"))
      (node (ref "C18") (pin "1") (pinfunction "1_1") (pintype "passive"))
      (node (ref "C19") (pin "1") (pinfunction "1_1") (pintype "passive"))
      (node (ref "C2") (pin "2") (pinfunction "2_2") (pintype "passive"))
      (node (ref "C20") (pin "1") (pinfunction "1_1") (pintype "passive"))
      (node (ref "C21") (pin "2") (pinfunction "2_2") (pintype "passive"))
      (node (ref "C22") (pin "2") (pinfunction "2_2") (pintype "passive"))
      (node (ref "C23") (pin "1") (pinfunction "1_1") (pintype "passive"))
      (node (ref "C3") (pin "2") (pinfunction "2_2") (pintype "passive"))
      (node (ref "C4") (pin "2") (pinfunction "2_2") (pintype "passive"))
      (node (ref "C5") (pin "2") (pinfunction "2_2") (pintype "passive"))
      (node (ref "C6") (pin "2") (pinfunction "2_2") (pintype "passive"))
      (node (ref "C7") (pin "2") (pinfunction "2_2") (pintype "passive"))
      (node (ref "C8") (pin "2") (pinfunction "2_2") (pintype "passive"))
      (node (ref "C9") (pin "2") (pinfunction "2_2") (pintype "passive"))
      (node (ref "D1") (pin "C") (pinfunction "C_C") (pintype "passive"))
      (node (ref "D2") (pin "C") (pinfunction "C_C") (pintype "passive"))
      (node (ref "D6") (pin "C") (pinfunction "C_C") (pintype "passive"))
      (node (ref "D7") (pin "C") (pinfunction "C_C") (pintype "passive"))
      (node (ref "H1") (pin "1") (pinfunction "GND_1") (pintype "passive"))
      (node (ref "H2") (pin "1") (pinfunction "GND_1") (pintype "passive"))
      (node (ref "IC1") (pin "1") (pinfunction "GND_1") (pintype "passive"))
      (node (ref "J1") (pin "2") (pinfunction "2_2") (pintype "passive"))
      (node (ref "J10") (pin "3") (pinfunction "3_3") (pintype "passive"))
      (node (ref "J11") (pin "2") (pinfunction "2_2") (pintype "passive"))
      (node (ref "J12") (pin "3") (pinfunction "3_3") (pintype "passive"))
      (node (ref "J12") (pin "5") (pinfunction "5_5") (pintype "passive"))
      (node (ref "J12") (pin "9") (pinfunction "9_9") (pintype "passive"))
      (node (ref "J2") (pin "2") (pinfunction "2_2") (pintype "passive"))
      (node (ref "J3") (pin "2") (pinfunction "2_2") (pintype "passive"))
      (node (ref "J4") (pin "2") (pinfunction "2_2") (pintype "passive"))
      (node (ref "J5") (pin "2") (pinfunction "2_2") (pintype "passive"))
      (node (ref "J6") (pin "5") (pinfunction "GND_5") (pintype "passive"))
      (node (ref "J7") (pin "2") (pinfunction "2_2") (pintype "passive"))
      (node (ref "J8") (pin "2") (pinfunction "2_2") (pintype "passive"))
      (node (ref "J9") (pin "2") (pinfunction "2_2") (pintype "passive"))
      (node (ref "P2") (pin "1") (pinfunction "1_1") (pintype "passive"))
      (node (ref "R16") (pin "1") (pinfunction "1_1") (pintype "passive"))
      (node (ref "SW1") (pin "2") (pintype "passive"))
      (node (ref "U1") (pin "16") (pinfunction "VSS_16") (pintype "passive"))
      (node (ref "U1") (pin "33") (pinfunction "GND_-_PAD_33") (pintype "passive"))
      (node (ref "U1") (pin "8") (pinfunction "VSSA_8") (pintype "passive"))
      (node (ref "U2") (pin "8") (pinfunction "GND_8") (pintype "passive"))
      (node (ref "U3") (pin "10") (pinfunction "VSS_10") (pintype "passive"))
      (node (ref "U4") (pin "11") (pinfunction "GND-PAD_11") (pintype "passive"))
      (node (ref "U4") (pin "3") (pinfunction "VSS_3") (pintype "passive"))
      (node (ref "U5") (pin "1") (pinfunction "GND_1") (pintype "passive"))
      (node (ref "U6") (pin "13") (pinfunction "GND_13") (pintype "passive"))
      (node (ref "U6") (pin "17") (pinfunction "GND-PAD_17") (pintype "passive"))
      (node (ref "U6") (pin "3") (pinfunction "GND_3") (pintype "passive"))
    )
    (net (code "39") (name "Net-(D1-PadA)") (class "Default")
      (node (ref "D1") (pin "A") (pinfunction "A_A") (pintype "passive"))
      (node (ref "R6") (pin "2") (pinfunction "2_2") (pintype "passive"))
    )
    (net (code "40") (name "Net-(D2-PadA)") (class "Default")
      (node (ref "D2") (pin "A") (pinfunction "A_A") (pintype "passive"))
      (node (ref "R7") (pin "2") (pinfunction "2_2") (pintype "passive"))
    )
    (net (code "41") (name "Net-(D3-A)") (class "Default")
      (node (ref "C19") (pin "2") (pinfunction "2_2") (pintype "passive"))
      (node (ref "D3") (pin "1") (pinfunction "A_1") (pintype "passive"))
      (node (ref "Q1") (pin "2") (pinfunction "S_2") (pintype "passive"))
      (node (ref "U5") (pin "3") (pinfunction "VIN_3") (pintype "passive"))
    )
    (net (code "42") (name "Net-(D3-K)") (class "Default")
      (node (ref "C18") (pin "2") (pinfunction "2_2") (pintype "passive"))
      (node (ref "C22") (pin "1") (pinfunction "1_1") (pintype "passive"))
      (node (ref "D3") (pin "2") (pinfunction "K_2") (pintype "passive"))
      (node (ref "J6") (pin "1") (pinfunction "VBUS_1") (pintype "passive"))
      (node (ref "J8") (pin "1") (pinfunction "1_1") (pintype "passive"))
      (node (ref "Q1") (pin "1") (pinfunction "G_1") (pintype "passive"))
      (node (ref "U4") (pin "1") (pinfunction "VBUS_1") (pintype "passive"))
      (node (ref "U6") (pin "10") (pinfunction "VCC_10") (pintype "passive"))
    )
    (net (code "43") (name "Net-(D4-PadA)") (class "Default")
      (node (ref "D4") (pin "A") (pinfunction "A_A") (pintype "passive"))
      (node (ref "R11") (pin "1") (pinfunction "1_1") (pintype "passive"))
    )
    (net (code "44") (name "Net-(D5-PadA)") (class "Default")
      (node (ref "D5") (pin "A") (pinfunction "A_A") (pintype "passive"))
      (node (ref "R13") (pin "1") (pinfunction "1_1") (pintype "passive"))
    )
    (net (code "45") (name "Net-(D6-PadA)") (class "Default")
      (node (ref "D6") (pin "A") (pinfunction "A_A") (pintype "passive"))
      (node (ref "R22") (pin "2") (pinfunction "2_2") (pintype "passive"))
    )
    (net (code "46") (name "Net-(D7-PadA)") (class "Default")
      (node (ref "D7") (pin "A") (pinfunction "A_A") (pintype "passive"))
      (node (ref "R23") (pin "1") (pinfunction "1_1") (pintype "passive"))
    )
    (net (code "47") (name "Net-(J6-DM)") (class "Default")
      (node (ref "J6") (pin "2") (pinfunction "DM_2") (pintype "passive"))
      (node (ref "R21") (pin "1") (pinfunction "1_1") (pintype "passive"))
    )
    (net (code "48") (name "Net-(J6-DP)") (class "Default")
      (node (ref "J6") (pin "3") (pinfunction "DP_3") (pintype "passive"))
      (node (ref "R20") (pin "1") (pinfunction "1_1") (pintype "passive"))
    )
    (net (code "49") (name "Net-(U1-VDDA)") (class "Default")
      (node (ref "C11") (pin "1") (pinfunction "1_1") (pintype "passive"))
      (node (ref "FB1") (pin "2") (pinfunction "2_2") (pintype "passive"))
      (node (ref "U1") (pin "7") (pinfunction "VDDA_7") (pintype "passive"))
    )
    (net (code "50") (name "Net-(U3-SCL1)") (class "Default")
      (node (ref "J5") (pin "4") (pinfunction "4_4") (pintype "passive"))
      (node (ref "R4") (pin "2") (pinfunction "2_2") (pintype "passive"))
      (node (ref "U3") (pin "5") (pinfunction "SCL1_5") (pintype "passive"))
    )
    (net (code "51") (name "Net-(U3-SCL2)") (class "Default")
      (node (ref "J7") (pin "4") (pinfunction "4_4") (pintype "passive"))
      (node (ref "R8") (pin "2") (pinfunction "2_2") (pintype "passive"))
      (node (ref "U3") (pin "8") (pinfunction "SCL2_8") (pintype "passive"))
    )
    (net (code "52") (name "Net-(U3-SCL3)") (class "Default")
      (node (ref "J9") (pin "4") (pinfunction "4_4") (pintype "passive"))
      (node (ref "R10") (pin "2") (pinfunction "2_2") (pintype "passive"))
      (node (ref "U3") (pin "12") (pinfunction "SCL3_12") (pintype "passive"))
    )
    (net (code "53") (name "Net-(U3-SCL4)") (class "Default")
      (node (ref "J11") (pin "4") (pinfunction "4_4") (pintype "passive"))
      (node (ref "R14") (pin "2") (pinfunction "2_2") (pintype "passive"))
      (node (ref "U3") (pin "15") (pinfunction "SCL4_15") (pintype "passive"))
    )
    (net (code "54") (name "Net-(U3-SDA1)") (class "Default")
      (node (ref "J5") (pin "3") (pinfunction "3_3") (pintype "passive"))
      (node (ref "R5") (pin "2") (pinfunction "2_2") (pintype "passive"))
      (node (ref "U3") (pin "6") (pinfunction "SDA1_6") (pintype "passive"))
    )
    (net (code "55") (name "Net-(U3-SDA2)") (class "Default")
      (node (ref "J7") (pin "3") (pinfunction "3_3") (pintype "passive"))
      (node (ref "R9") (pin "2") (pinfunction "2_2") (pintype "passive"))
      (node (ref "U3") (pin "9") (pinfunction "SDA2_9") (pintype "passive"))
    )
    (net (code "56") (name "Net-(U3-SDA3)") (class "Default")
      (node (ref "J9") (pin "3") (pinfunction "3_3") (pintype "passive"))
      (node (ref "R12") (pin "2") (pinfunction "2_2") (pintype "passive"))
      (node (ref "U3") (pin "13") (pinfunction "SDA3_13") (pintype "passive"))
    )
    (net (code "57") (name "Net-(U3-SDA4)") (class "Default")
      (node (ref "J11") (pin "3") (pinfunction "3_3") (pintype "passive"))
      (node (ref "R15") (pin "2") (pinfunction "2_2") (pintype "passive"))
      (node (ref "U3") (pin "16") (pinfunction "SDA4_16") (pintype "passive"))
    )
    (net (code "58") (name "Net-(U4-ISET)") (class "Default")
      (node (ref "R16") (pin "2") (pinfunction "2_2") (pintype "passive"))
      (node (ref "U4") (pin "2") (pinfunction "ISET_2") (pintype "passive"))
    )
    (net (code "59") (name "Net-(U4-VTSB)") (class "Default")
      (node (ref "R17") (pin "2") (pinfunction "2_2") (pintype "passive"))
      (node (ref "U4") (pin "4") (pinfunction "VTSB_4") (pintype "passive"))
    )
    (net (code "60") (name "Net-(U4-~{CHG})") (class "Default")
      (node (ref "D4") (pin "C") (pinfunction "C_C") (pintype "passive"))
      (node (ref "U4") (pin "8") (pinfunction "~{CHG}_8") (pintype "passive"))
    )
    (net (code "61") (name "Net-(U4-~{EN})") (class "Default")
      (node (ref "D5") (pin "C") (pinfunction "C_C") (pintype "passive"))
      (node (ref "U4") (pin "6") (pinfunction "~{PG}_6") (pintype "passive"))
      (node (ref "U4") (pin "7") (pinfunction "~{EN}_7") (pintype "passive"))
    )
    (net (code "62") (name "Net-(U6-3V3OUT)") (class "Default")
      (node (ref "C21") (pin "1") (pinfunction "1_1") (pintype "passive"))
      (node (ref "U6") (pin "1") (pinfunction "VCCIO_1") (pintype "passive"))
      (node (ref "U6") (pin "8") (pinfunction "3V3OUT_8") (pintype "passive"))
      (node (ref "U6") (pin "9") (pinfunction "RESET#_9") (pintype "passive"))
    )
    (net (code "63") (name "Net-(U6-CBUS2)") (class "Default")
      (node (ref "R22") (pin "1") (pinfunction "1_1") (pintype "passive"))
      (node (ref "U6") (pin "5") (pinfunction "CBUS2_5") (pintype "passive"))
    )
    (net (code "64") (name "Net-(U6-CBUS4)") (class "Default")
      (node (ref "R23") (pin "2") (pinfunction "2_2") (pintype "passive"))
      (node (ref "U6") (pin "4") (pinfunction "CBUS4_4") (pintype "passive"))
    )
    (net (code "65") (name "Net-(U6-USBDM)") (class "Default")
      (node (ref "R21") (pin "2") (pinfunction "2_2") (pintype "passive"))
      (node (ref "U6") (pin "7") (pinfunction "USBDM_7") (pintype "passive"))
    )
    (net (code "66") (name "Net-(U6-USBDP)") (class "Default")
      (node (ref "R20") (pin "2") (pinfunction "2_2") (pintype "passive"))
      (node (ref "U6") (pin "6") (pinfunction "USBDP_6") (pintype "passive"))
    )
    (net (code "67") (name "unconnected-(IC1-GPIO0-Pad6)") (class "Default")
      (node (ref "IC1") (pin "6") (pinfunction "GPIO0_6") (pintype "passive"))
    )
    (net (code "68") (name "unconnected-(IC1-GPIO15-Pad5)") (class "Default")
      (node (ref "IC1") (pin "5") (pinfunction "GPIO15_5") (pintype "passive"))
    )
    (net (code "69") (name "unconnected-(J6-ID-Pad4)") (class "Default")
      (node (ref "J6") (pin "4") (pinfunction "ID_4") (pintype "passive"))
    )
    (net (code "70") (name "unconnected-(J12-Pad6)") (class "Default")
      (node (ref "J12") (pin "6") (pinfunction "6_6") (pintype "passive"))
    )
    (net (code "71") (name "unconnected-(J12-Pad7)") (class "Default")
      (node (ref "J12") (pin "7") (pinfunction "7_7") (pintype "passive"))
    )
    (net (code "72") (name "unconnected-(J12-Pad8)") (class "Default")
      (node (ref "J12") (pin "8") (pinfunction "8_8") (pintype "passive"))
    )
    (net (code "73") (name "unconnected-(U1-PTA4_{slash}_NMI_b_{slash}_I2C1_SDA_{slash}_TPM0_CH1-Pad14)") (class "Default")
      (node (ref "U1") (pin "14") (pinfunction "PTA4_/_NMI_b_/_I2C1_SDA_/_TPM0_CH1_14") (pintype "passive"))
    )
    (net (code "74") (name "unconnected-(U1-PTB0_{slash}_LLWU_P5_{slash}_ADC0_SE8_{slash}_I2C0_SDA_{slash}_TPM1_CH1-Pad20)") (class "Default")
      (node (ref "U1") (pin "20") (pinfunction "PTB0_/_LLWU_P5_/_ADC0_SE8_/_I2C0_SDA_/_TPM1_CH1_20") (pintype "passive"))
    )
    (net (code "75") (name "unconnected-(U1-PTC3_{slash}_LLWU_P7_{slash}_SPI1_SCK_{slash}_UART1_RX_{slash}_TPM0_CH2_{slash}_CLKOUT-Pad24)") (class "Default")
      (node (ref "U1") (pin "24") (pinfunction "PTC3_/_LLWU_P7_/_SPI1_SCK_/_UART1_RX_/_TPM0_CH2_/_CLKOUT_24") (pintype "passive"))
    )
    (net (code "76") (name "unconnected-(U1-PTC7_{slash}_CMP0_IN1_{slash}_SPI0_MISO_{slash}_SPI0_MOSI-Pad28)") (class "Default")
      (node (ref "U1") (pin "28") (pinfunction "PTC7_/_CMP0_IN1_/_SPI0_MISO_/_SPI0_MOSI_28") (pintype "passive"))
    )
    (net (code "77") (name "unconnected-(U1-PTE17_{slash}_ADC0_DM1{slash}SE5a_{slash}_SPI0_SCK_{slash}_UART2_RX_{slash}_TPM_CLKIN1_{slash}_LPTMR0_ALT3_{slash}_FXIO0_D1-Pad4)") (class "Default")
      (node (ref "U1") (pin "4") (pinfunction "PTE17_/_ADC0_DM1/SE5a_/_SPI0_SCK_/_UART2_RX_/_TPM_CLKIN1_/_LPTMR0_ALT3_/_FXIO0_D1_4") (pintype "passive"))
    )
    (net (code "78") (name "unconnected-(U1-PTE30_{slash}_DAC0_OUT_{slash}_ADC0_SE23_{slash}_CMP0_IN4_{slash}_TPM0_CH2_{slash}_TPM_CLKIN0-Pad9)") (class "Default")
      (node (ref "U1") (pin "9") (pinfunction "PTE30_/_DAC0_OUT_/_ADC0_SE23_/_CMP0_IN4_/_TPM0_CH2_/_TPM_CLKIN0_9") (pintype "passive"))
    )
    (net (code "79") (name "unconnected-(U2-VEE-Pad7)") (class "Default")
      (node (ref "U2") (pin "7") (pinfunction "VEE_7") (pintype "passive"))
    )
    (net (code "80") (name "unconnected-(U3-EXPSCL1-Pad1)") (class "Default")
      (node (ref "U3") (pin "1") (pinfunction "EXPSCL1_1") (pintype "passive"))
    )
    (net (code "81") (name "unconnected-(U3-EXPSCL2-Pad2)") (class "Default")
      (node (ref "U3") (pin "2") (pinfunction "EXPSCL2_2") (pintype "passive"))
    )
    (net (code "82") (name "unconnected-(U3-EXPSDA1-Pad18)") (class "Default")
      (node (ref "U3") (pin "18") (pinfunction "EXPSDA1_18") (pintype "passive"))
    )
    (net (code "83") (name "unconnected-(U3-EXPSDA2-Pad19)") (class "Default")
      (node (ref "U3") (pin "19") (pinfunction "EXPSDA2_19") (pintype "passive"))
    )
    (net (code "84") (name "unconnected-(U4-VDPM-Pad9)") (class "Default")
      (node (ref "U4") (pin "9") (pinfunction "VDPM_9") (pintype "passive"))
    )
    (net (code "85") (name "unconnected-(U6-CBUS0-Pad12)") (class "Default")
      (node (ref "U6") (pin "12") (pinfunction "CBUS0_12") (pintype "passive"))
    )
    (net (code "86") (name "unconnected-(U6-CBUS1-Pad11)") (class "Default")
      (node (ref "U6") (pin "11") (pinfunction "CBUS1_11") (pintype "passive"))
    )
    (net (code "87") (name "unconnected-(U6-CBUS3-Pad14)") (class "Default")
      (node (ref "U6") (pin "14") (pinfunction "CBUS3_14") (pintype "passive"))
    )
    (net (code "88") (name "unconnected-(U6-CBUS5-Pad15)") (class "Default")
      (node (ref "U6") (pin "15") (pinfunction "CBUS5_15") (pintype "passive"))
    )
  )
)
